# adruinoIO.net
KiCad netlist of a schematic drawn in EAGLE
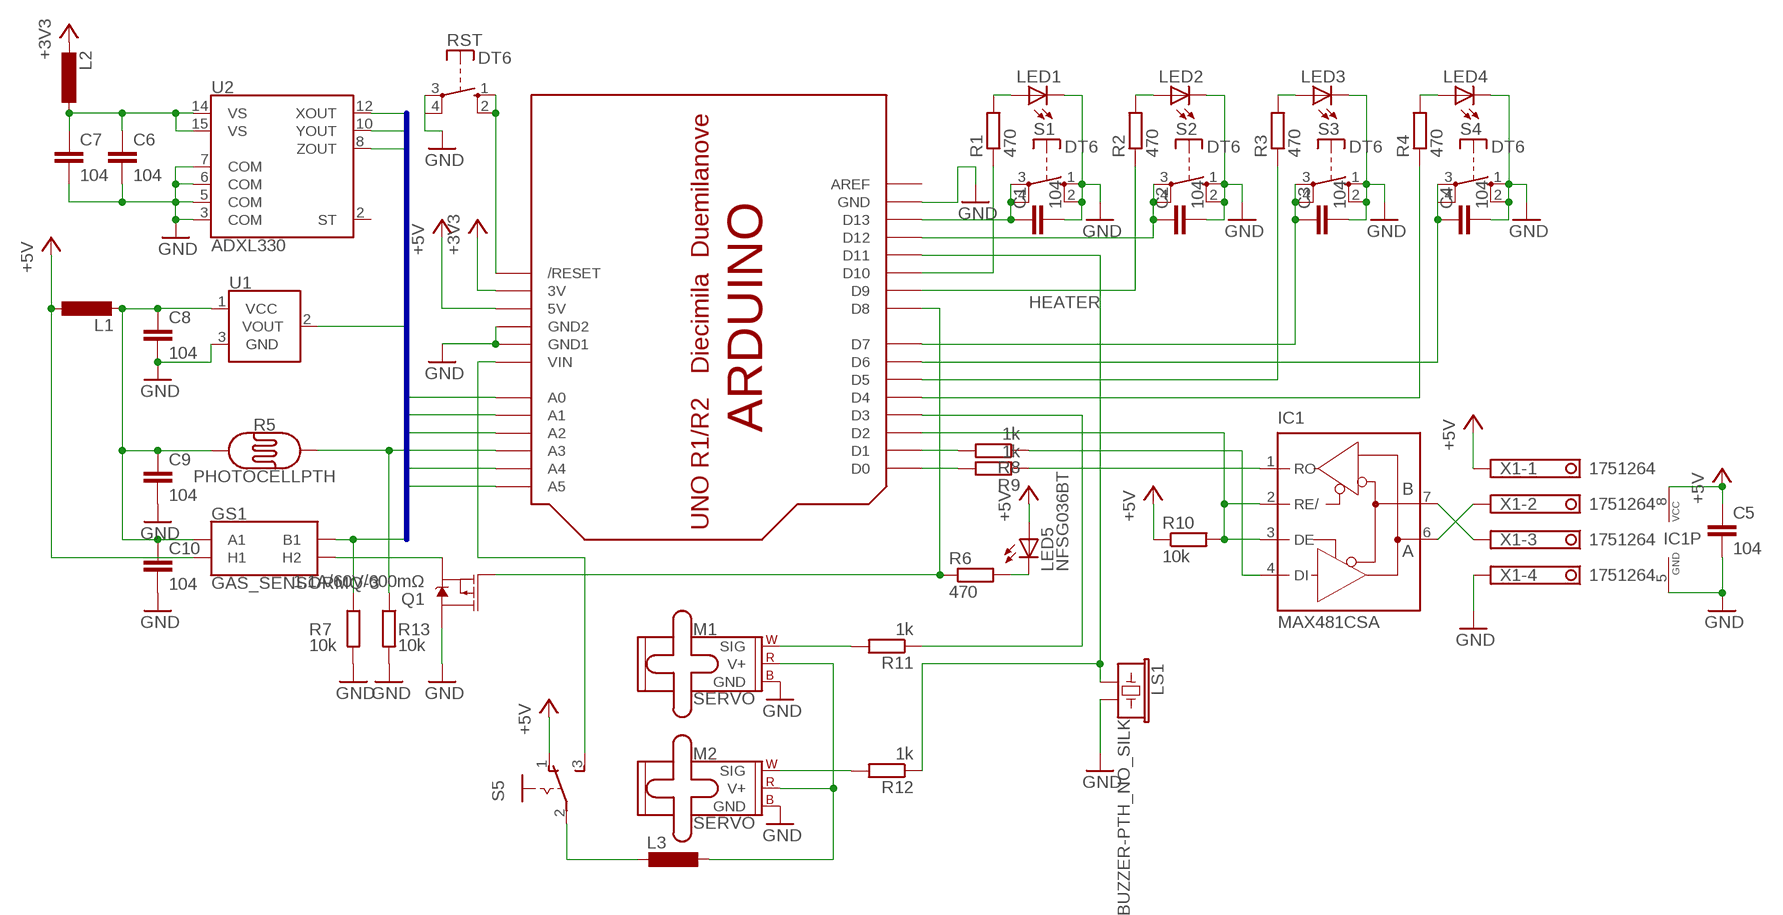
[diagram p0: schematic, sheet 1]

(export (version "E")
  (design (tool "Eeschema 10.0.6"))
  (components
    (comp (ref "C1")
      (value "104")
      (footprint "eagle-import:C1206")
      (libsource (lib "eagle-import") (part "C-EUC1206"))
    )
    (comp (ref "C2")
      (value "104")
      (footprint "eagle-import:C1206")
      (libsource (lib "eagle-import") (part "C-EUC1206"))
    )
    (comp (ref "C3")
      (value "104")
      (footprint "eagle-import:C1206")
      (libsource (lib "eagle-import") (part "C-EUC1206"))
    )
    (comp (ref "C4")
      (value "104")
      (footprint "eagle-import:C1206")
      (libsource (lib "eagle-import") (part "C-EUC1206"))
    )
    (comp (ref "C5")
      (value "104")
      (footprint "eagle-import:C1206")
      (libsource (lib "eagle-import") (part "C-EUC1206"))
    )
    (comp (ref "C6")
      (value "104")
      (footprint "eagle-import:C1206")
      (libsource (lib "eagle-import") (part "C-EUC1206"))
    )
    (comp (ref "C7")
      (value "104")
      (footprint "eagle-import:C1206")
      (libsource (lib "eagle-import") (part "C-EUC1206"))
    )
    (comp (ref "C8")
      (value "104")
      (footprint "eagle-import:C1206")
      (libsource (lib "eagle-import") (part "C-EUC1206"))
    )
    (comp (ref "C9")
      (value "104")
      (footprint "eagle-import:C1206K")
      (libsource (lib "eagle-import") (part "C-EUC1206K"))
    )
    (comp (ref "C10")
      (value "104")
      (footprint "eagle-import:C1206")
      (libsource (lib "eagle-import") (part "C-EUC1206"))
    )
    (comp (ref "GS1")
      (value "GAS_SENSORMQ-3")
      (footprint "eagle-import:GAS_SENSOR")
      (libsource (lib "eagle-import") (part "GAS_SENSORMQ-3"))
    )
    (comp (ref "IC1")
      (value "MAX481CSA")
      (footprint "eagle-import:SO08")
      (fields (field (name "MF") "MAXIM"))
      (libsource (lib "eagle-import") (part "MAX481CSA"))
    )
    (comp (ref "L1")
      (value "L-EUL2012C")
      (footprint "eagle-import:L2012C")
      (libsource (lib "eagle-import") (part "L-EUL2012C"))
    )
    (comp (ref "L2")
      (value "L-EUL2012C")
      (footprint "eagle-import:L2012C")
      (libsource (lib "eagle-import") (part "L-EUL2012C"))
    )
    (comp (ref "L3")
      (value "L-EUL2012C")
      (footprint "eagle-import:L2012C")
      (libsource (lib "eagle-import") (part "L-EUL2012C"))
    )
    (comp (ref "LED1")
      (value "NFSG036BT")
      (footprint "eagle-import:NFSG036BT")
      (libsource (lib "eagle-import") (part "NFSG036BT"))
    )
    (comp (ref "LED2")
      (value "NFSG036BT")
      (footprint "eagle-import:NFSG036BT")
      (libsource (lib "eagle-import") (part "NFSG036BT"))
    )
    (comp (ref "LED3")
      (value "NFSG036BT")
      (footprint "eagle-import:NFSG036BT")
      (libsource (lib "eagle-import") (part "NFSG036BT"))
    )
    (comp (ref "LED4")
      (value "NFSG036BT")
      (footprint "eagle-import:NFSG036BT")
      (libsource (lib "eagle-import") (part "NFSG036BT"))
    )
    (comp (ref "LED5")
      (value "NFSG036BT")
      (footprint "eagle-import:NFSG036BT")
      (libsource (lib "eagle-import") (part "NFSG036BT"))
    )
    (comp (ref "LS1")
      (value "BUZZER-PTH_NO_SILK")
      (footprint "eagle-import:BUZZER-12MM-NS")
      (libsource (lib "eagle-import") (part "BUZZER-PTH_NO_SILK"))
    )
    (comp (ref "M1")
      (value "SERVO")
      (footprint "eagle-import:1X03")
      (libsource (lib "eagle-import") (part "SERVO"))
    )
    (comp (ref "M2")
      (value "SERVO")
      (footprint "eagle-import:1X03")
      (libsource (lib "eagle-import") (part "SERVO"))
    )
    (comp (ref "Q1")
      (value "1.1A/60V/600mΩ")
      (footprint "eagle-import:SOT23-3")
      (libsource (lib "eagle-import") (part "MOSFET_PCH-SI2309DS"))
    )
    (comp (ref "R1")
      (value "470")
      (footprint "eagle-import:R1206")
      (libsource (lib "eagle-import") (part "R-EU_R1206"))
    )
    (comp (ref "R2")
      (value "470")
      (footprint "eagle-import:R1206")
      (libsource (lib "eagle-import") (part "R-EU_R1206"))
    )
    (comp (ref "R3")
      (value "470")
      (footprint "eagle-import:R1206")
      (libsource (lib "eagle-import") (part "R-EU_R1206"))
    )
    (comp (ref "R4")
      (value "470")
      (footprint "eagle-import:R1206")
      (libsource (lib "eagle-import") (part "R-EU_R1206"))
    )
    (comp (ref "R5")
      (value "PHOTOCELLPTH")
      (footprint "eagle-import:PHOTOCELL")
      (libsource (lib "eagle-import") (part "PHOTOCELLPTH"))
    )
    (comp (ref "R6")
      (value "470")
      (footprint "eagle-import:R1206")
      (libsource (lib "eagle-import") (part "R-EU_R1206"))
    )
    (comp (ref "R7")
      (value "10k")
      (footprint "eagle-import:R1206")
      (libsource (lib "eagle-import") (part "R-EU_R1206"))
    )
    (comp (ref "R8")
      (value "1k")
      (footprint "eagle-import:R1206")
      (libsource (lib "eagle-import") (part "R-EU_R1206"))
    )
    (comp (ref "R9")
      (value "1k")
      (footprint "eagle-import:R1206")
      (libsource (lib "eagle-import") (part "R-EU_R1206"))
    )
    (comp (ref "R10")
      (value "10k")
      (footprint "eagle-import:R1206")
      (libsource (lib "eagle-import") (part "R-EU_R1206"))
    )
    (comp (ref "R11")
      (value "1k")
      (footprint "eagle-import:R1206")
      (libsource (lib "eagle-import") (part "R-EU_R1206"))
    )
    (comp (ref "R12")
      (value "1k")
      (footprint "eagle-import:R1206")
      (libsource (lib "eagle-import") (part "R-EU_R1206"))
    )
    (comp (ref "R13")
      (value "10k")
      (footprint "eagle-import:R1206")
      (libsource (lib "eagle-import") (part "R-EU_R1206"))
    )
    (comp (ref "RST")
      (value "DT6")
      (footprint "eagle-import:DT6")
      (libsource (lib "eagle-import") (part "DT6"))
    )
    (comp (ref "S1")
      (value "DT6")
      (footprint "eagle-import:DT6")
      (libsource (lib "eagle-import") (part "DT6"))
    )
    (comp (ref "S2")
      (value "DT6")
      (footprint "eagle-import:DT6")
      (libsource (lib "eagle-import") (part "DT6"))
    )
    (comp (ref "S3")
      (value "DT6")
      (footprint "eagle-import:DT6")
      (libsource (lib "eagle-import") (part "DT6"))
    )
    (comp (ref "S4")
      (value "DT6")
      (footprint "eagle-import:DT6")
      (libsource (lib "eagle-import") (part "DT6"))
    )
    (comp (ref "S5")
      (value "255SB")
      (footprint "eagle-import:255SB")
      (libsource (lib "eagle-import") (part "255SB"))
    )
    (comp (ref "U$1")
      (value "ARDUINO-NOHOLE")
      (footprint "eagle-import:ARDUINO-NOHOLE")
      (libsource (lib "eagle-import") (part "ARDUINO-NOHOLE"))
    )
    (comp (ref "U1")
      (value "TMP36GT9")
      (footprint "eagle-import:TO-92")
      (libsource (lib "eagle-import") (part "TMP36GT9"))
    )
    (comp (ref "U2")
      (value "ADXL330")
      (footprint "eagle-import:LFCSP-16-4X4")
      (libsource (lib "eagle-import") (part "ADXL330"))
    )
    (comp (ref "X1")
      (value "1751264")
      (footprint "eagle-import:1751264")
      (libsource (lib "eagle-import") (part "1751264"))
    )
  )
  (nets
    (net (code "1") (name "+3V3") (class "Default")
      (node (ref "L2") (pin "2") (pinfunction "2_2") (pintype "passive"))
      (node (ref "U$1") (pin "3V") (pinfunction "3V_3V") (pintype "power_in"))
    )
    (net (code "2") (name "+5V") (class "Default")
      (node (ref "C5") (pin "1") (pinfunction "1_1") (pintype "passive"))
      (node (ref "GS1") (pin "HA") (pinfunction "H1_HA") (pintype "bidirectional"))
      (node (ref "IC1") (pin "8") (pinfunction "VCC_8") (pintype "power_in"))
      (node (ref "L1") (pin "1") (pinfunction "1_1") (pintype "passive"))
      (node (ref "LED5") (pin "A") (pinfunction "A_A") (pintype "passive"))
      (node (ref "R10") (pin "1") (pinfunction "1_1") (pintype "passive"))
      (node (ref "S5") (pin "1") (pinfunction "O_1") (pintype "passive"))
      (node (ref "U$1") (pin "5V") (pinfunction "5V_5V") (pintype "power_in"))
      (node (ref "X1") (pin "1") (pinfunction "K_1") (pintype "passive"))
    )
    (net (code "3") (name "/A0") (class "Default")
      (node (ref "R13") (pin "1") (pinfunction "1_1") (pintype "passive"))
      (node (ref "R5") (pin "2") (pinfunction "P$2_2") (pintype "bidirectional"))
      (node (ref "U$1") (pin "A0") (pinfunction "A0_A0") (pintype "bidirectional"))
    )
    (net (code "4") (name "/A1") (class "Default")
      (node (ref "U$1") (pin "A1") (pinfunction "A1_A1") (pintype "bidirectional"))
      (node (ref "U1") (pin "2") (pinfunction "VOUT_2") (pintype "bidirectional"))
    )
    (net (code "5") (name "/A2") (class "Default")
      (node (ref "GS1") (pin "B1") (pinfunction "B1_B1") (pintype "bidirectional"))
      (node (ref "R7") (pin "1") (pinfunction "1_1") (pintype "passive"))
      (node (ref "U$1") (pin "A2") (pinfunction "A2_A2") (pintype "bidirectional"))
    )
    (net (code "6") (name "/A3") (class "Default")
      (node (ref "U$1") (pin "A3") (pinfunction "A3_A3") (pintype "bidirectional"))
      (node (ref "U2") (pin "8") (pinfunction "ZOUT_8") (pintype "bidirectional"))
    )
    (net (code "7") (name "/A4") (class "Default")
      (node (ref "U$1") (pin "A4") (pinfunction "A4_A4") (pintype "bidirectional"))
      (node (ref "U2") (pin "10") (pinfunction "YOUT_10") (pintype "bidirectional"))
    )
    (net (code "8") (name "/A5") (class "Default")
      (node (ref "U$1") (pin "A5") (pinfunction "A5_A5") (pintype "bidirectional"))
      (node (ref "U2") (pin "12") (pinfunction "XOUT_12") (pintype "bidirectional"))
    )
    (net (code "9") (name "/HEATER") (class "Default")
      (node (ref "Q1") (pin "1") (pinfunction "G_1") (pintype "bidirectional"))
      (node (ref "R6") (pin "1") (pinfunction "1_1") (pintype "passive"))
      (node (ref "U$1") (pin "D8") (pinfunction "D8_D8") (pintype "bidirectional"))
    )
    (net (code "10") (name "GND") (class "Default")
      (node (ref "C1") (pin "2") (pinfunction "2_2") (pintype "passive"))
      (node (ref "C10") (pin "2") (pinfunction "2_2") (pintype "passive"))
      (node (ref "C2") (pin "2") (pinfunction "2_2") (pintype "passive"))
      (node (ref "C3") (pin "2") (pinfunction "2_2") (pintype "passive"))
      (node (ref "C4") (pin "2") (pinfunction "2_2") (pintype "passive"))
      (node (ref "C5") (pin "2") (pinfunction "2_2") (pintype "passive"))
      (node (ref "C6") (pin "2") (pinfunction "2_2") (pintype "passive"))
      (node (ref "C7") (pin "2") (pinfunction "2_2") (pintype "passive"))
      (node (ref "C8") (pin "2") (pinfunction "2_2") (pintype "passive"))
      (node (ref "C9") (pin "2") (pinfunction "2_2") (pintype "passive"))
      (node (ref "IC1") (pin "5") (pinfunction "GND_5") (pintype "power_in"))
      (node (ref "LED1") (pin "C") (pinfunction "C_C") (pintype "passive"))
      (node (ref "LED2") (pin "C") (pinfunction "C_C") (pintype "passive"))
      (node (ref "LED3") (pin "C") (pinfunction "C_C") (pintype "passive"))
      (node (ref "LED4") (pin "C") (pinfunction "C_C") (pintype "passive"))
      (node (ref "LS1") (pin "-") (pinfunction "2_-") (pintype "passive"))
      (node (ref "M1") (pin "3") (pinfunction "GND_3") (pintype "bidirectional"))
      (node (ref "M2") (pin "3") (pinfunction "GND_3") (pintype "bidirectional"))
      (node (ref "Q1") (pin "3") (pinfunction "D_3") (pintype "bidirectional"))
      (node (ref "R13") (pin "2") (pinfunction "2_2") (pintype "passive"))
      (node (ref "R7") (pin "2") (pinfunction "2_2") (pintype "passive"))
      (node (ref "RST") (pin "3") (pinfunction "P_3") (pintype "passive"))
      (node (ref "RST") (pin "4") (pinfunction "P_4") (pintype "passive"))
      (node (ref "S1") (pin "1") (pinfunction "S_1") (pintype "passive"))
      (node (ref "S1") (pin "2") (pinfunction "S_2") (pintype "passive"))
      (node (ref "S2") (pin "1") (pinfunction "S_1") (pintype "passive"))
      (node (ref "S2") (pin "2") (pinfunction "S_2") (pintype "passive"))
      (node (ref "S3") (pin "1") (pinfunction "S_1") (pintype "passive"))
      (node (ref "S3") (pin "2") (pinfunction "S_2") (pintype "passive"))
      (node (ref "S4") (pin "1") (pinfunction "S_1") (pintype "passive"))
      (node (ref "S4") (pin "2") (pinfunction "S_2") (pintype "passive"))
      (node (ref "U$1") (pin "GND") (pinfunction "GND_GND") (pintype "power_in"))
      (node (ref "U$1") (pin "GND1") (pinfunction "GND1_GND1") (pintype "power_in"))
      (node (ref "U$1") (pin "GND2") (pinfunction "GND2_GND2") (pintype "power_in"))
      (node (ref "U1") (pin "3") (pinfunction "GND_3") (pintype "bidirectional"))
      (node (ref "U2") (pin "3") (pinfunction "COM_3") (pintype "bidirectional"))
      (node (ref "U2") (pin "5") (pinfunction "COM_5") (pintype "bidirectional"))
      (node (ref "U2") (pin "6") (pinfunction "COM_6") (pintype "bidirectional"))
      (node (ref "U2") (pin "7") (pinfunction "COM_7") (pintype "bidirectional"))
      (node (ref "X1") (pin "4") (pinfunction "K_4") (pintype "passive"))
    )
    (net (code "11") (name "Net-(C1-Pad1)") (class "Default")
      (node (ref "C1") (pin "1") (pinfunction "1_1") (pintype "passive"))
      (node (ref "S1") (pin "3") (pinfunction "P_3") (pintype "passive"))
      (node (ref "S1") (pin "4") (pinfunction "P_4") (pintype "passive"))
      (node (ref "U$1") (pin "D13") (pinfunction "D13_D13") (pintype "bidirectional"))
    )
    (net (code "12") (name "Net-(C2-Pad1)") (class "Default")
      (node (ref "C2") (pin "1") (pinfunction "1_1") (pintype "passive"))
      (node (ref "S2") (pin "3") (pinfunction "P_3") (pintype "passive"))
      (node (ref "S2") (pin "4") (pinfunction "P_4") (pintype "passive"))
      (node (ref "U$1") (pin "D12") (pinfunction "D12_D12") (pintype "bidirectional"))
    )
    (net (code "13") (name "Net-(C3-Pad1)") (class "Default")
      (node (ref "C3") (pin "1") (pinfunction "1_1") (pintype "passive"))
      (node (ref "S3") (pin "3") (pinfunction "P_3") (pintype "passive"))
      (node (ref "S3") (pin "4") (pinfunction "P_4") (pintype "passive"))
      (node (ref "U$1") (pin "D7") (pinfunction "D7_D7") (pintype "bidirectional"))
    )
    (net (code "14") (name "Net-(C4-Pad1)") (class "Default")
      (node (ref "C4") (pin "1") (pinfunction "1_1") (pintype "passive"))
      (node (ref "S4") (pin "3") (pinfunction "P_3") (pintype "passive"))
      (node (ref "S4") (pin "4") (pinfunction "P_4") (pintype "passive"))
      (node (ref "U$1") (pin "D6") (pinfunction "D6_D6") (pintype "bidirectional"))
    )
    (net (code "15") (name "Net-(C6-Pad1)") (class "Default")
      (node (ref "C6") (pin "1") (pinfunction "1_1") (pintype "passive"))
      (node (ref "C7") (pin "1") (pinfunction "1_1") (pintype "passive"))
      (node (ref "L2") (pin "1") (pinfunction "1_1") (pintype "passive"))
      (node (ref "U2") (pin "14") (pinfunction "VS_14") (pintype "bidirectional"))
      (node (ref "U2") (pin "15") (pinfunction "VS_15") (pintype "bidirectional"))
    )
    (net (code "16") (name "Net-(GS1-H2)") (class "Default")
      (node (ref "GS1") (pin "HB") (pinfunction "H2_HB") (pintype "bidirectional"))
      (node (ref "Q1") (pin "2") (pinfunction "S_2") (pintype "bidirectional"))
    )
    (net (code "17") (name "Net-(IC1A-A)") (class "Default")
      (node (ref "IC1") (pin "6") (pinfunction "A_6") (pintype "passive"))
      (node (ref "X1") (pin "2") (pinfunction "K_2") (pintype "passive"))
    )
    (net (code "18") (name "Net-(IC1A-B)") (class "Default")
      (node (ref "IC1") (pin "7") (pinfunction "B_7") (pintype "passive"))
      (node (ref "X1") (pin "3") (pinfunction "K_3") (pintype "passive"))
    )
    (net (code "19") (name "Net-(IC1A-DE)") (class "Default")
      (node (ref "IC1") (pin "2") (pinfunction "RE/_2") (pintype "input"))
      (node (ref "IC1") (pin "3") (pinfunction "DE_3") (pintype "input"))
      (node (ref "R10") (pin "2") (pinfunction "2_2") (pintype "passive"))
      (node (ref "U$1") (pin "D2") (pinfunction "D2_D2") (pintype "bidirectional"))
    )
    (net (code "20") (name "Net-(IC1A-DI)") (class "Default")
      (node (ref "IC1") (pin "4") (pinfunction "DI_4") (pintype "input"))
      (node (ref "R8") (pin "1") (pinfunction "1_1") (pintype "passive"))
    )
    (net (code "21") (name "Net-(IC1A-RO)") (class "Default")
      (node (ref "IC1") (pin "1") (pinfunction "RO_1") (pintype "output"))
      (node (ref "R9") (pin "1") (pinfunction "1_1") (pintype "passive"))
    )
    (net (code "22") (name "Net-(LED1-PadA)") (class "Default")
      (node (ref "LED1") (pin "A") (pinfunction "A_A") (pintype "passive"))
      (node (ref "R1") (pin "2") (pinfunction "2_2") (pintype "passive"))
    )
    (net (code "23") (name "Net-(LED2-PadA)") (class "Default")
      (node (ref "LED2") (pin "A") (pinfunction "A_A") (pintype "passive"))
      (node (ref "R2") (pin "2") (pinfunction "2_2") (pintype "passive"))
    )
    (net (code "24") (name "Net-(LED3-PadA)") (class "Default")
      (node (ref "LED3") (pin "A") (pinfunction "A_A") (pintype "passive"))
      (node (ref "R3") (pin "2") (pinfunction "2_2") (pintype "passive"))
    )
    (net (code "25") (name "Net-(LED4-PadA)") (class "Default")
      (node (ref "LED4") (pin "A") (pinfunction "A_A") (pintype "passive"))
      (node (ref "R4") (pin "2") (pinfunction "2_2") (pintype "passive"))
    )
    (net (code "26") (name "Net-(LED5-PadC)") (class "Default")
      (node (ref "LED5") (pin "C") (pinfunction "C_C") (pintype "passive"))
      (node (ref "R6") (pin "2") (pinfunction "2_2") (pintype "passive"))
    )
    (net (code "27") (name "Net-(LS1-1)") (class "Default")
      (node (ref "LS1") (pin "+") (pinfunction "1_+") (pintype "passive"))
      (node (ref "R12") (pin "1") (pinfunction "1_1") (pintype "passive"))
      (node (ref "U$1") (pin "D11") (pinfunction "D11_D11") (pintype "bidirectional"))
    )
    (net (code "28") (name "Net-(M1-SIG)") (class "Default")
      (node (ref "M1") (pin "1") (pinfunction "SIG_1") (pintype "bidirectional"))
      (node (ref "R11") (pin "2") (pinfunction "2_2") (pintype "passive"))
    )
    (net (code "29") (name "Net-(M1-V+)") (class "Default")
      (node (ref "L3") (pin "1") (pinfunction "1_1") (pintype "passive"))
      (node (ref "M1") (pin "2") (pinfunction "V+_2") (pintype "bidirectional"))
      (node (ref "M2") (pin "2") (pinfunction "V+_2") (pintype "bidirectional"))
    )
    (net (code "30") (name "Net-(M2-SIG)") (class "Default")
      (node (ref "M2") (pin "1") (pinfunction "SIG_1") (pintype "bidirectional"))
      (node (ref "R12") (pin "2") (pinfunction "2_2") (pintype "passive"))
    )
    (net (code "31") (name "Net-(R1-Pad1)") (class "Default")
      (node (ref "R1") (pin "1") (pinfunction "1_1") (pintype "passive"))
      (node (ref "U$1") (pin "D10") (pinfunction "D10_D10") (pintype "bidirectional"))
    )
    (net (code "32") (name "Net-(R2-Pad1)") (class "Default")
      (node (ref "R2") (pin "1") (pinfunction "1_1") (pintype "passive"))
      (node (ref "U$1") (pin "D9") (pinfunction "D9_D9") (pintype "bidirectional"))
    )
    (net (code "33") (name "Net-(R3-Pad1)") (class "Default")
      (node (ref "R3") (pin "1") (pinfunction "1_1") (pintype "passive"))
      (node (ref "U$1") (pin "D5") (pinfunction "D5_D5") (pintype "bidirectional"))
    )
    (net (code "34") (name "Net-(R4-Pad1)") (class "Default")
      (node (ref "R4") (pin "1") (pinfunction "1_1") (pintype "passive"))
      (node (ref "U$1") (pin "D4") (pinfunction "D4_D4") (pintype "bidirectional"))
    )
    (net (code "35") (name "Net-(R5-P$1)") (class "Default")
      (node (ref "C10") (pin "1") (pinfunction "1_1") (pintype "passive"))
      (node (ref "C8") (pin "1") (pinfunction "1_1") (pintype "passive"))
      (node (ref "C9") (pin "1") (pinfunction "1_1") (pintype "passive"))
      (node (ref "GS1") (pin "A1") (pinfunction "A1_A1") (pintype "bidirectional"))
      (node (ref "L1") (pin "2") (pinfunction "2_2") (pintype "passive"))
      (node (ref "R5") (pin "1") (pinfunction "P$1_1") (pintype "bidirectional"))
      (node (ref "U1") (pin "1") (pinfunction "VCC_1") (pintype "bidirectional"))
    )
    (net (code "36") (name "Net-(R8-Pad2)") (class "Default")
      (node (ref "R8") (pin "2") (pinfunction "2_2") (pintype "passive"))
      (node (ref "U$1") (pin "D1") (pinfunction "D1_D1") (pintype "bidirectional"))
    )
    (net (code "37") (name "Net-(R9-Pad2)") (class "Default")
      (node (ref "R9") (pin "2") (pinfunction "2_2") (pintype "passive"))
      (node (ref "U$1") (pin "D0") (pinfunction "D0_D0") (pintype "bidirectional"))
    )
    (net (code "38") (name "Net-(R11-Pad1)") (class "Default")
      (node (ref "R11") (pin "1") (pinfunction "1_1") (pintype "passive"))
      (node (ref "U$1") (pin "D3") (pinfunction "D3_D3") (pintype "bidirectional"))
    )
    (net (code "39") (name "Net-(S5-P)") (class "Default")
      (node (ref "L3") (pin "2") (pinfunction "2_2") (pintype "passive"))
      (node (ref "S5") (pin "2") (pinfunction "P_2") (pintype "passive"))
    )
    (net (code "40") (name "Net-(S5-S)") (class "Default")
      (node (ref "S5") (pin "3") (pinfunction "S_3") (pintype "passive"))
      (node (ref "U$1") (pin "VIN") (pinfunction "VIN_VIN") (pintype "power_in"))
    )
    (net (code "41") (name "Net-(U$1-{slash}RESET)") (class "Default")
      (node (ref "RST") (pin "1") (pinfunction "S_1") (pintype "passive"))
      (node (ref "RST") (pin "2") (pinfunction "S_2") (pintype "passive"))
      (node (ref "U$1") (pin "RESET") (pinfunction "/RESET_RESET") (pintype "bidirectional"))
    )
    (net (code "42") (name "unconnected-(U$1-PadAREF)") (class "Default")
      (node (ref "U$1") (pin "AREF") (pinfunction "AREF_AREF") (pintype "bidirectional"))
    )
    (net (code "43") (name "unconnected-(U2-ST-Pad2)") (class "Default")
      (node (ref "U2") (pin "2") (pinfunction "ST_2") (pintype "bidirectional"))
    )
  )
)
